# Regbot.net
KiCad netlist of a schematic drawn in EAGLE
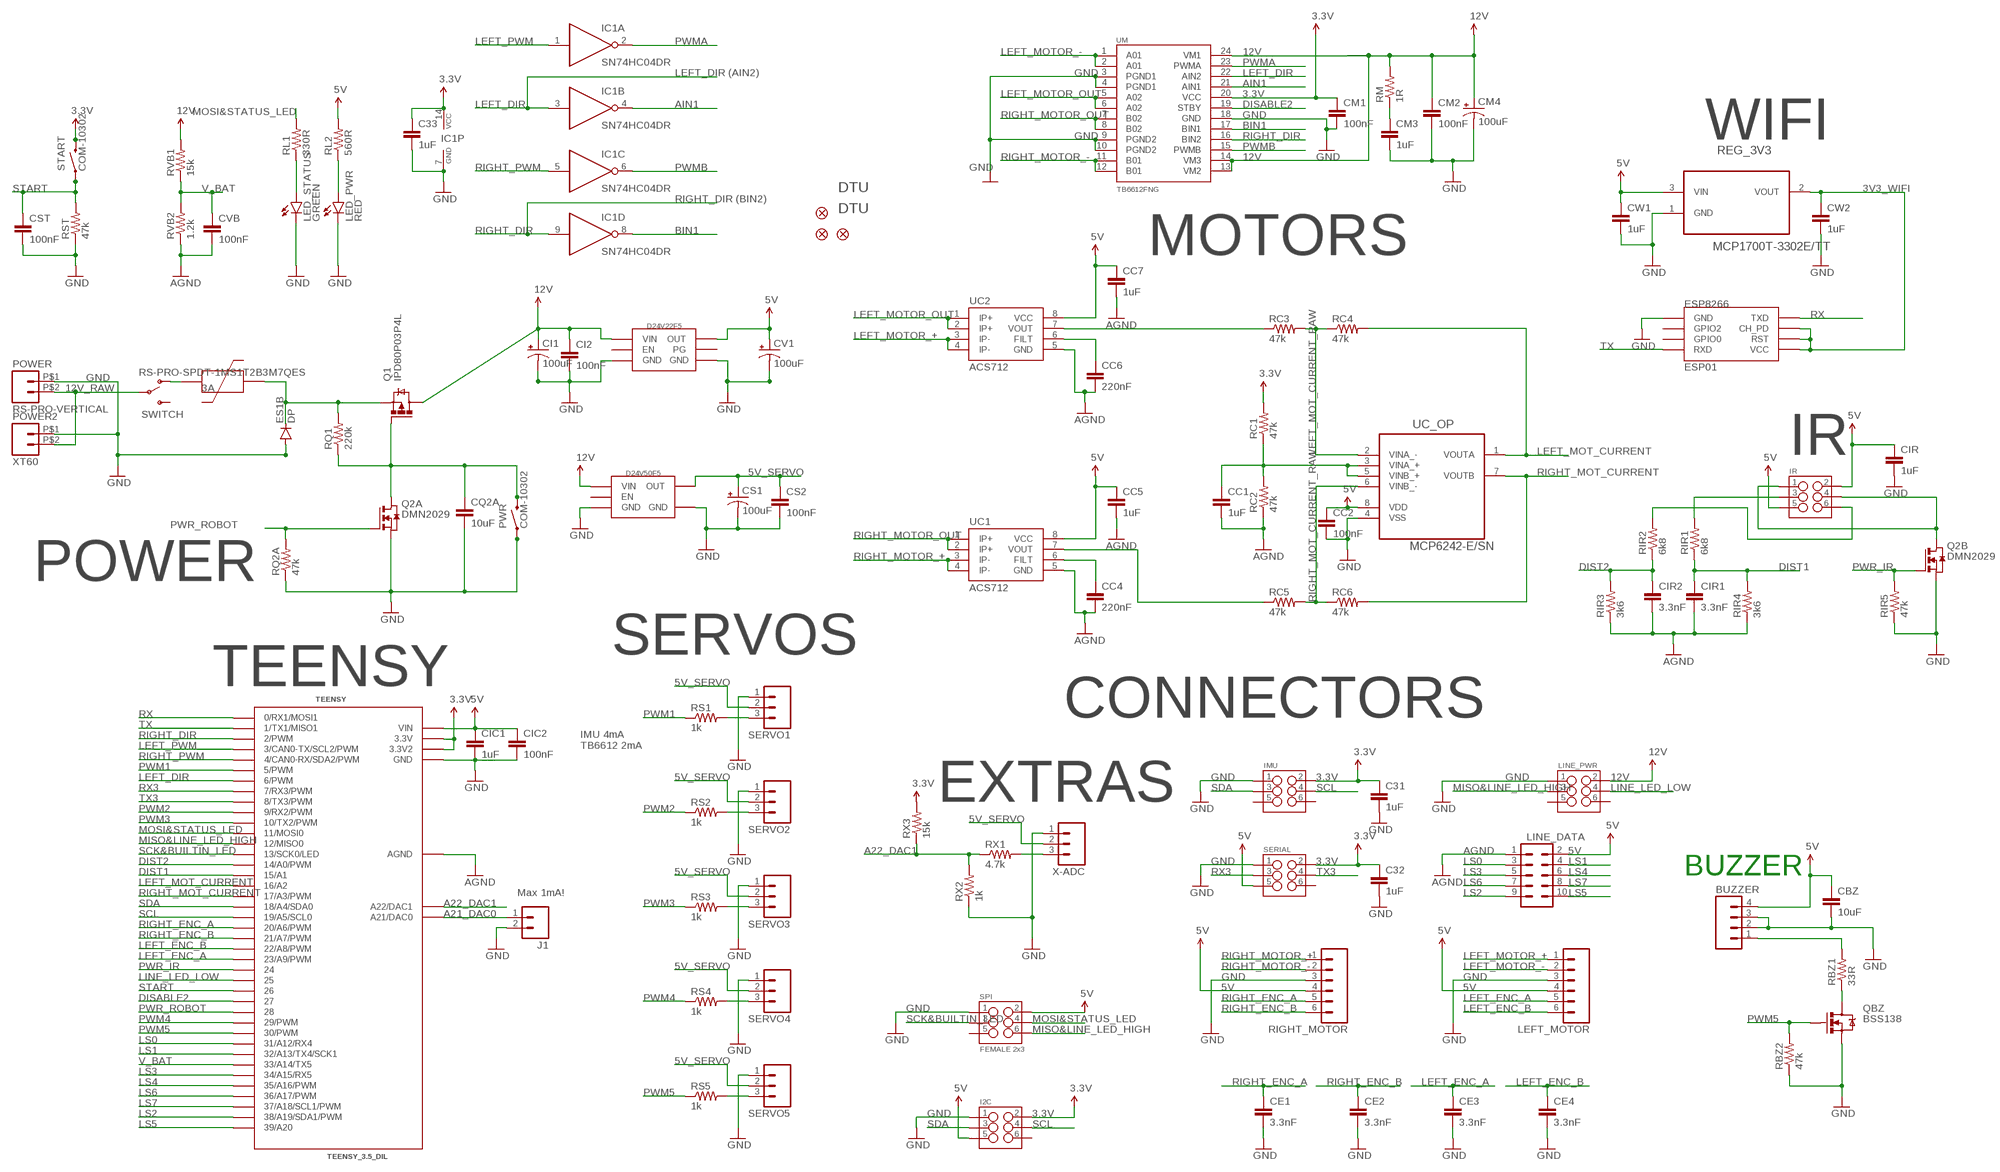
[diagram p0: schematic, sheet 1]

(export (version "E")
  (design (tool "Eeschema 10.0.6"))
  (components
    (comp (ref "BUZZER")
      (value "M04POLAR")
      (footprint "eagle-import:MOLEX-1X4")
      (libsource (lib "eagle-import") (part "M04POLAR"))
    )
    (comp (ref "C31")
      (value "1uF")
      (footprint "eagle-import:0805")
      (libsource (lib "eagle-import") (part "SparkFun-Passives_CAP0805"))
    )
    (comp (ref "C32")
      (value "1uF")
      (footprint "eagle-import:0805")
      (libsource (lib "eagle-import") (part "CAP0805"))
    )
    (comp (ref "C33")
      (value "1uF")
      (footprint "eagle-import:0805")
      (libsource (lib "eagle-import") (part "CAP0805"))
    )
    (comp (ref "CBZ")
      (value "10uF")
      (footprint "eagle-import:1210")
      (libsource (lib "eagle-import") (part "CAP1210"))
    )
    (comp (ref "CC1")
      (value "1uF")
      (footprint "eagle-import:0805")
      (libsource (lib "eagle-import") (part "SparkFun-Passives_CAP0805"))
    )
    (comp (ref "CC2")
      (value "100nF")
      (footprint "eagle-import:0805")
      (libsource (lib "eagle-import") (part "SparkFun-Passives_CAP0805"))
    )
    (comp (ref "CC4")
      (value "220nF")
      (footprint "eagle-import:0805")
      (libsource (lib "eagle-import") (part "SparkFun-Passives_CAP0805"))
    )
    (comp (ref "CC5")
      (value "1uF")
      (footprint "eagle-import:0805")
      (libsource (lib "eagle-import") (part "SparkFun-Passives_CAP0805"))
    )
    (comp (ref "CC6")
      (value "220nF")
      (footprint "eagle-import:0805")
      (libsource (lib "eagle-import") (part "SparkFun-Passives_CAP0805"))
    )
    (comp (ref "CC7")
      (value "1uF")
      (footprint "eagle-import:0805")
      (libsource (lib "eagle-import") (part "SparkFun-Passives_CAP0805"))
    )
    (comp (ref "CE1")
      (value "3.3nF")
      (footprint "eagle-import:0805")
      (libsource (lib "eagle-import") (part "SparkFun-Passives_CAP0805"))
    )
    (comp (ref "CE2")
      (value "3.3nF")
      (footprint "eagle-import:0805")
      (libsource (lib "eagle-import") (part "SparkFun-Passives_CAP0805"))
    )
    (comp (ref "CE3")
      (value "3.3nF")
      (footprint "eagle-import:0805")
      (libsource (lib "eagle-import") (part "SparkFun-Passives_CAP0805"))
    )
    (comp (ref "CE4")
      (value "3.3nF")
      (footprint "eagle-import:0805")
      (libsource (lib "eagle-import") (part "SparkFun-Passives_CAP0805"))
    )
    (comp (ref "CI1")
      (value "100uF")
      (footprint "eagle-import:PANASONIC_D_XL")
      (libsource (lib "eagle-import") (part "PANASONIC_D"))
    )
    (comp (ref "CI2")
      (value "100nF")
      (footprint "eagle-import:0805")
      (libsource (lib "eagle-import") (part "SparkFun-Passives_CAP0805"))
    )
    (comp (ref "CIC1")
      (value "1uF")
      (footprint "eagle-import:0805")
      (libsource (lib "eagle-import") (part "CAP0805"))
    )
    (comp (ref "CIC2")
      (value "100nF")
      (footprint "eagle-import:0805")
      (libsource (lib "eagle-import") (part "SparkFun-Passives_CAP0805"))
    )
    (comp (ref "CIR")
      (value "1uF")
      (footprint "eagle-import:0805")
      (libsource (lib "eagle-import") (part "SparkFun-Passives_CAP0805"))
    )
    (comp (ref "CIR1")
      (value "3.3nF")
      (footprint "eagle-import:0805")
      (libsource (lib "eagle-import") (part "SparkFun-Passives_CAP0805"))
    )
    (comp (ref "CIR2")
      (value "3.3nF")
      (footprint "eagle-import:0805")
      (libsource (lib "eagle-import") (part "SparkFun-Passives_CAP0805"))
    )
    (comp (ref "CM1")
      (value "100nF")
      (footprint "eagle-import:0805")
      (libsource (lib "eagle-import") (part "SparkFun-Passives_CAP0805"))
    )
    (comp (ref "CM2")
      (value "100nF")
      (footprint "eagle-import:0805")
      (libsource (lib "eagle-import") (part "SparkFun-Passives_CAP0805"))
    )
    (comp (ref "CM3")
      (value "1uF")
      (footprint "eagle-import:0805")
      (libsource (lib "eagle-import") (part "SparkFun-Passives_CAP0805"))
    )
    (comp (ref "CM4")
      (value "100uF")
      (footprint "eagle-import:PANASONIC_D_XL")
      (libsource (lib "eagle-import") (part "PANASONIC_D"))
    )
    (comp (ref "CQ2A")
      (value "10uF")
      (footprint "eagle-import:1210")
      (libsource (lib "eagle-import") (part "CAP1210"))
    )
    (comp (ref "CS1")
      (value "100uF")
      (footprint "eagle-import:PANASONIC_D_XL")
      (libsource (lib "eagle-import") (part "PANASONIC_D"))
    )
    (comp (ref "CS2")
      (value "100nF")
      (footprint "eagle-import:0805")
      (libsource (lib "eagle-import") (part "SparkFun-Passives_CAP0805"))
    )
    (comp (ref "CST")
      (value "100nF")
      (footprint "eagle-import:0805")
      (libsource (lib "eagle-import") (part "SparkFun-Passives_CAP0805"))
    )
    (comp (ref "CV1")
      (value "100uF")
      (footprint "eagle-import:PANASONIC_D_XL")
      (libsource (lib "eagle-import") (part "PANASONIC_D"))
    )
    (comp (ref "CVB")
      (value "100nF")
      (footprint "eagle-import:0805")
      (libsource (lib "eagle-import") (part "SparkFun-Passives_CAP0805"))
    )
    (comp (ref "CW1")
      (value "1uF")
      (footprint "eagle-import:0805")
      (libsource (lib "eagle-import") (part "SparkFun-Passives_CAP0805"))
    )
    (comp (ref "CW2")
      (value "1uF")
      (footprint "eagle-import:0805")
      (libsource (lib "eagle-import") (part "SparkFun-Passives_CAP0805"))
    )
    (comp (ref "D24V22F5")
      (value "POLOLU_D24V22")
      (footprint "eagle-import:D24V22")
      (libsource (lib "eagle-import") (part "POLOLU_D24V22"))
    )
    (comp (ref "D24V50F5")
      (value "POLOLU_D24V50")
      (footprint "eagle-import:D24V50")
      (libsource (lib "eagle-import") (part "POLOLU_D24V50"))
    )
    (comp (ref "DP")
      (value "ES1B")
      (footprint "eagle-import:SMA-DIODE")
      (libsource (lib "eagle-import") (part "DIODESMA"))
    )
    (comp (ref "ESP8266")
      (value "ESP01")
      (footprint "eagle-import:ESP01")
      (libsource (lib "eagle-import") (part "ESP01"))
    )
    (comp (ref "FD1")
      (value "FIDUCIAL1X2")
      (footprint "eagle-import:FIDUCIAL-1X2")
      (libsource (lib "eagle-import") (part "FIDUCIAL1X2"))
    )
    (comp (ref "FD2")
      (value "FIDUCIAL1X2")
      (footprint "eagle-import:FIDUCIAL-1X2")
      (libsource (lib "eagle-import") (part "FIDUCIAL1X2"))
    )
    (comp (ref "FD3")
      (value "FIDUCIAL1X2")
      (footprint "eagle-import:FIDUCIAL-1X2")
      (libsource (lib "eagle-import") (part "FIDUCIAL1X2"))
    )
    (comp (ref "I2C")
      (value "M03X2SHROUD")
      (footprint "eagle-import:2X3-SHROUDED")
      (libsource (lib "eagle-import") (part "M03X2SHROUD"))
    )
    (comp (ref "IC1")
      (value "SN74HC04DR")
      (footprint "eagle-import:SO14")
      (libsource (lib "eagle-import") (part "7404DHC"))
    )
    (comp (ref "IMU")
      (value "M03X2SHROUD")
      (footprint "eagle-import:2X3-SHROUDED")
      (libsource (lib "eagle-import") (part "M03X2SHROUD"))
    )
    (comp (ref "IR")
      (value "M03X2SHROUD")
      (footprint "eagle-import:2X3-SHROUDED")
      (libsource (lib "eagle-import") (part "M03X2SHROUD"))
    )
    (comp (ref "J1")
      (value "M02PTH")
      (footprint "eagle-import:1X02")
      (libsource (lib "eagle-import") (part "M02PTH"))
    )
    (comp (ref "LED_PWR")
      (value "RED")
      (footprint "eagle-import:LED-1206")
      (libsource (lib "eagle-import") (part "LED1206"))
    )
    (comp (ref "LED_STATUS")
      (value "GREEN")
      (footprint "eagle-import:LED-1206")
      (libsource (lib "eagle-import") (part "LED1206"))
    )
    (comp (ref "LEFT_MOTOR")
      (value "M06SILK_FEMALE_PTH")
      (footprint "eagle-import:1X06")
      (libsource (lib "eagle-import") (part "M06SILK_FEMALE_PTH"))
    )
    (comp (ref "LINE_DATA")
      (value "M05X2SHD")
      (footprint "eagle-import:2X5-SHROUDED")
      (libsource (lib "eagle-import") (part "M05X2SHD"))
    )
    (comp (ref "LINE_PWR")
      (value "M03X2SHROUD")
      (footprint "eagle-import:2X3-SHROUDED")
      (libsource (lib "eagle-import") (part "M03X2SHROUD"))
    )
    (comp (ref "MAIN_FUSE")
      (value "SMF_OMNI-BLOK_FUSE_BLOCK")
      (footprint "eagle-import:SMF_OMNI-BLOK_FUSE_BLOCK")
      (libsource (lib "eagle-import") (part "SMF_OMNI-BLOK_FUSE_BLOCK"))
    )
    (comp (ref "POWER")
      (value "RS-PRO-VERTICAL")
      (footprint "eagle-import:RS-PRO-VERTICAL")
      (fields (field (name "PURPOSE") "DYSE"))
      (libsource (lib "eagle-import") (part "RS-PRO-VERTICAL"))
    )
    (comp (ref "POWER2")
      (value "XT60")
      (footprint "eagle-import:XT60")
      (libsource (lib "eagle-import") (part "XT60"))
    )
    (comp (ref "PWR")
      (value "COM-10302")
      (footprint "eagle-import:TACTILE-PTH-12MM")
      (libsource (lib "eagle-import") (part "SWITCH-MOMENTARY"))
    )
    (comp (ref "Q1")
      (value "IPD80P03P4L")
      (footprint "eagle-import:D-PAK_TO252AA")
      (libsource (lib "eagle-import") (part "IRF?5305R"))
    )
    (comp (ref "Q2")
      (value "DMN2029")
      (footprint "eagle-import:SO8")
      (libsource (lib "eagle-import") (part "NMOS2SO8"))
    )
    (comp (ref "QBZ")
      (value "BSS138")
      (footprint "eagle-import:SOT23")
      (fields (field (name "PROD_ID") "TRANS-00830"))
      (libsource (lib "eagle-import") (part "MOSFET-NCHANNELBSS138"))
    )
    (comp (ref "RBZ1")
      (value "33R")
      (footprint "eagle-import:0805")
      (libsource (lib "eagle-import") (part "RESISTOR0805-RES"))
    )
    (comp (ref "RBZ2")
      (value "47k")
      (footprint "eagle-import:0805")
      (libsource (lib "eagle-import") (part "RESISTOR0805-RES"))
    )
    (comp (ref "RC1")
      (value "47k")
      (footprint "eagle-import:0805")
      (libsource (lib "eagle-import") (part "RESISTOR0805-RES"))
    )
    (comp (ref "RC2")
      (value "47k")
      (footprint "eagle-import:0805")
      (libsource (lib "eagle-import") (part "RESISTOR0805-RES"))
    )
    (comp (ref "RC3")
      (value "47k")
      (footprint "eagle-import:0805")
      (libsource (lib "eagle-import") (part "RESISTOR0805-RES"))
    )
    (comp (ref "RC4")
      (value "47k")
      (footprint "eagle-import:0805")
      (libsource (lib "eagle-import") (part "RESISTOR0805-RES"))
    )
    (comp (ref "RC5")
      (value "47k")
      (footprint "eagle-import:0805")
      (libsource (lib "eagle-import") (part "RESISTOR0805-RES"))
    )
    (comp (ref "RC6")
      (value "47k")
      (footprint "eagle-import:0805")
      (libsource (lib "eagle-import") (part "RESISTOR0805-RES"))
    )
    (comp (ref "REG_3V3")
      (value "MCP1700T-3302E/TT")
      (footprint "eagle-import:SOT95P237X112-3N")
      (libsource (lib "eagle-import") (part "MCP1700T-3302E/TT"))
    )
    (comp (ref "RIGHT_MOTOR")
      (value "M06SILK_FEMALE_PTH")
      (footprint "eagle-import:1X06")
      (libsource (lib "eagle-import") (part "M06SILK_FEMALE_PTH"))
    )
    (comp (ref "RIR1")
      (value "6k8")
      (footprint "eagle-import:0805")
      (libsource (lib "eagle-import") (part "RESISTOR0805-RES"))
    )
    (comp (ref "RIR2")
      (value "6k8")
      (footprint "eagle-import:0805")
      (libsource (lib "eagle-import") (part "RESISTOR0805-RES"))
    )
    (comp (ref "RIR3")
      (value "3k6")
      (footprint "eagle-import:0805")
      (libsource (lib "eagle-import") (part "RESISTOR0805-RES"))
    )
    (comp (ref "RIR4")
      (value "3k6")
      (footprint "eagle-import:0805")
      (libsource (lib "eagle-import") (part "RESISTOR0805-RES"))
    )
    (comp (ref "RIR5")
      (value "47k")
      (footprint "eagle-import:0805")
      (libsource (lib "eagle-import") (part "RESISTOR0805-RES"))
    )
    (comp (ref "RL1")
      (value "330R")
      (footprint "eagle-import:0805")
      (libsource (lib "eagle-import") (part "RESISTOR0805-RES"))
    )
    (comp (ref "RL2")
      (value "560R")
      (footprint "eagle-import:0805")
      (libsource (lib "eagle-import") (part "RESISTOR0805-RES"))
    )
    (comp (ref "RM")
      (value "1R")
      (footprint "eagle-import:0805")
      (libsource (lib "eagle-import") (part "RESISTOR0805-RES"))
    )
    (comp (ref "RQ1")
      (value "220k")
      (footprint "eagle-import:0805")
      (libsource (lib "eagle-import") (part "RESISTOR0805-RES"))
    )
    (comp (ref "RQ2A")
      (value "47k")
      (footprint "eagle-import:0805")
      (libsource (lib "eagle-import") (part "RESISTOR0805-RES"))
    )
    (comp (ref "RS1")
      (value "1k")
      (footprint "eagle-import:0805")
      (libsource (lib "eagle-import") (part "RESISTOR0805-RES"))
    )
    (comp (ref "RS2")
      (value "1k")
      (footprint "eagle-import:0805")
      (libsource (lib "eagle-import") (part "RESISTOR0805-RES"))
    )
    (comp (ref "RS3")
      (value "1k")
      (footprint "eagle-import:0805")
      (libsource (lib "eagle-import") (part "RESISTOR0805-RES"))
    )
    (comp (ref "RS4")
      (value "1k")
      (footprint "eagle-import:0805")
      (libsource (lib "eagle-import") (part "RESISTOR0805-RES"))
    )
    (comp (ref "RS5")
      (value "1k")
      (footprint "eagle-import:0805")
      (libsource (lib "eagle-import") (part "RESISTOR0805-RES"))
    )
    (comp (ref "RST")
      (value "47k")
      (footprint "eagle-import:0805")
      (libsource (lib "eagle-import") (part "RESISTOR0805-RES"))
    )
    (comp (ref "RVB1")
      (value "15k")
      (footprint "eagle-import:0805")
      (libsource (lib "eagle-import") (part "RESISTOR0805-RES"))
    )
    (comp (ref "RVB2")
      (value "1.2k")
      (footprint "eagle-import:0805")
      (libsource (lib "eagle-import") (part "RESISTOR0805-RES"))
    )
    (comp (ref "RX1")
      (value "4.7k")
      (footprint "eagle-import:0805")
      (libsource (lib "eagle-import") (part "RESISTOR0805-RES"))
    )
    (comp (ref "RX2")
      (value "1k")
      (footprint "eagle-import:0805")
      (libsource (lib "eagle-import") (part "RESISTOR0805-RES"))
    )
    (comp (ref "RX3")
      (value "15k")
      (footprint "eagle-import:0805")
      (libsource (lib "eagle-import") (part "RESISTOR0805-RES"))
    )
    (comp (ref "SERIAL")
      (value "M03X2SHROUD")
      (footprint "eagle-import:2X3-SHROUDED")
      (libsource (lib "eagle-import") (part "M03X2SHROUD"))
    )
    (comp (ref "SERVO1")
      (value "M03POLAR")
      (footprint "eagle-import:MOLEX-1X3")
      (libsource (lib "eagle-import") (part "M03POLAR"))
    )
    (comp (ref "SERVO2")
      (value "M03POLAR")
      (footprint "eagle-import:MOLEX-1X3")
      (libsource (lib "eagle-import") (part "M03POLAR"))
    )
    (comp (ref "SERVO3")
      (value "M03POLAR")
      (footprint "eagle-import:MOLEX-1X3")
      (libsource (lib "eagle-import") (part "M03POLAR"))
    )
    (comp (ref "SERVO4")
      (value "M03POLAR")
      (footprint "eagle-import:MOLEX-1X3")
      (libsource (lib "eagle-import") (part "M03POLAR"))
    )
    (comp (ref "SERVO5")
      (value "M03POLAR")
      (footprint "eagle-import:MOLEX-1X3")
      (libsource (lib "eagle-import") (part "M03POLAR"))
    )
    (comp (ref "SPI")
      (value "FEMALE 2x3")
      (footprint "eagle-import:2X3")
      (libsource (lib "eagle-import") (part "M03X2FEMALE"))
    )
    (comp (ref "START")
      (value "COM-10302")
      (footprint "eagle-import:TACTILE-PTH-12MM")
      (libsource (lib "eagle-import") (part "SWITCH-MOMENTARY"))
    )
    (comp (ref "SWITCH")
      (value "RS-PRO-SPDT-1MS1T2B3M7QES")
      (footprint "eagle-import:RS-PRO-1MS1T2B3M7QES")
      (libsource (lib "eagle-import") (part "RS-PRO-SPDT-1MS1T2B3M7QES"))
    )
    (comp (ref "TEENSY")
      (value "TEENSY_3.5_DIL")
      (footprint "eagle-import:TEENSY_3.5_DIL")
      (libsource (lib "eagle-import") (part "TEENSY_3.5_DIL"))
    )
    (comp (ref "U$1")
      (value "DTUMEDIUM-9MM")
      (footprint "eagle-import:DTU-MEDIUM-9MM")
      (libsource (lib "eagle-import") (part "DTUMEDIUM-9MM"))
    )
    (comp (ref "U$2")
      (value "DTULARGE")
      (footprint "eagle-import:DTU-LARGE")
      (libsource (lib "eagle-import") (part "DTULARGE"))
    )
    (comp (ref "UC1")
      (value "ACS712")
      (footprint "eagle-import:SO08")
      (libsource (lib "eagle-import") (part "ACS712"))
    )
    (comp (ref "UC2")
      (value "ACS712")
      (footprint "eagle-import:SO08")
      (libsource (lib "eagle-import") (part "ACS712"))
    )
    (comp (ref "UC_OP")
      (value "MCP6242-E/SN")
      (footprint "eagle-import:SOIC127P600X175-8N")
      (libsource (lib "eagle-import") (part "MCP6242-E/SN"))
    )
    (comp (ref "UM")
      (value "TB6612FNG")
      (footprint "eagle-import:SSOP24")
      (libsource (lib "eagle-import") (part "TB6612FNG"))
    )
    (comp (ref "X-ADC")
      (value "M03POLAR")
      (footprint "eagle-import:MOLEX-1X3")
      (libsource (lib "eagle-import") (part "M03POLAR"))
    )
  )
  (nets
    (net (code "1") (name "/3V3_WIFI") (class "Default")
      (node (ref "CW2") (pin "1") (pinfunction "1_1") (pintype "passive"))
      (node (ref "ESP8266") (pin "CH_PD") (pinfunction "CH_PD_CH_PD") (pintype "bidirectional"))
      (node (ref "ESP8266") (pin "RST") (pinfunction "RST_RST") (pintype "bidirectional"))
      (node (ref "ESP8266") (pin "VCC") (pinfunction "VCC_VCC") (pintype "bidirectional"))
      (node (ref "REG_3V3") (pin "2") (pinfunction "VOUT_2") (pintype "output"))
    )
    (net (code "2") (name "/5V_SERVO") (class "Default")
      (node (ref "CS1") (pin "+") (pinfunction "+_+") (pintype "passive"))
      (node (ref "CS2") (pin "1") (pinfunction "1_1") (pintype "passive"))
      (node (ref "D24V50F5") (pin "P$OUT") (pinfunction "OUT_P$OUT") (pintype "bidirectional"))
      (node (ref "SERVO1") (pin "2") (pinfunction "2_2") (pintype "passive"))
      (node (ref "SERVO2") (pin "2") (pinfunction "2_2") (pintype "passive"))
      (node (ref "SERVO3") (pin "2") (pinfunction "2_2") (pintype "passive"))
      (node (ref "SERVO4") (pin "2") (pinfunction "2_2") (pintype "passive"))
      (node (ref "SERVO5") (pin "2") (pinfunction "2_2") (pintype "passive"))
      (node (ref "X-ADC") (pin "2") (pinfunction "2_2") (pintype "passive"))
    )
    (net (code "3") (name "/12V_RAW") (class "Default")
      (node (ref "POWER") (pin "P$2") (pinfunction "2_P$2") (pintype "passive"))
      (node (ref "POWER2") (pin "P$2") (pinfunction "2_P$2") (pintype "passive"))
      (node (ref "SWITCH") (pin "P$2") (pinfunction "P2_P$2") (pintype "passive"))
    )
    (net (code "4") (name "/A21_DAC0") (class "Default")
      (node (ref "J1") (pin "1") (pinfunction "1_1") (pintype "passive"))
      (node (ref "TEENSY") (pin "A21") (pinfunction "A21/DAC0_A21") (pintype "bidirectional"))
    )
    (net (code "5") (name "/A22_DAC1") (class "Default")
      (node (ref "RX1") (pin "1") (pinfunction "1_1") (pintype "passive"))
      (node (ref "RX2") (pin "2") (pinfunction "2_2") (pintype "passive"))
      (node (ref "RX3") (pin "1") (pinfunction "1_1") (pintype "passive"))
      (node (ref "TEENSY") (pin "A22") (pinfunction "A22/DAC1_A22") (pintype "bidirectional"))
    )
    (net (code "6") (name "/AIN1") (class "Default")
      (node (ref "IC1") (pin "4") (pinfunction "O_4") (pintype "output"))
      (node (ref "UM") (pin "21") (pinfunction "AIN1_21") (pintype "bidirectional"))
    )
    (net (code "7") (name "/BIN1") (class "Default")
      (node (ref "IC1") (pin "8") (pinfunction "O_8") (pintype "output"))
      (node (ref "UM") (pin "17") (pinfunction "BIN1_17") (pintype "bidirectional"))
    )
    (net (code "8") (name "/DISABLE2") (class "Default")
      (node (ref "TEENSY") (pin "27") (pinfunction "27_27") (pintype "bidirectional"))
      (node (ref "UM") (pin "19") (pinfunction "STBY_19") (pintype "bidirectional"))
    )
    (net (code "9") (name "/DIST1") (class "Default")
      (node (ref "CIR1") (pin "1") (pinfunction "1_1") (pintype "passive"))
      (node (ref "RIR1") (pin "1") (pinfunction "1_1") (pintype "passive"))
      (node (ref "RIR4") (pin "2") (pinfunction "2_2") (pintype "passive"))
      (node (ref "TEENSY") (pin "15/A1") (pinfunction "15/A1_15/A1") (pintype "bidirectional"))
    )
    (net (code "10") (name "/DIST2") (class "Default")
      (node (ref "CIR2") (pin "1") (pinfunction "1_1") (pintype "passive"))
      (node (ref "RIR2") (pin "1") (pinfunction "1_1") (pintype "passive"))
      (node (ref "RIR3") (pin "2") (pinfunction "2_2") (pintype "passive"))
      (node (ref "TEENSY") (pin "14/A0") (pinfunction "14/A0/PWM_14/A0") (pintype "bidirectional"))
    )
    (net (code "11") (name "/LEFT_DIR") (class "Default")
      (node (ref "IC1") (pin "3") (pinfunction "I_3") (pintype "input"))
      (node (ref "TEENSY") (pin "6") (pinfunction "6/PWM_6") (pintype "bidirectional"))
      (node (ref "UM") (pin "22") (pinfunction "AIN2_22") (pintype "bidirectional"))
    )
    (net (code "12") (name "/LEFT_ENC_A") (class "Default")
      (node (ref "CE3") (pin "1") (pinfunction "1_1") (pintype "passive"))
      (node (ref "LEFT_MOTOR") (pin "5") (pinfunction "5_5") (pintype "passive"))
      (node (ref "TEENSY") (pin "23/A9") (pinfunction "23/A9/PWM_23/A9") (pintype "bidirectional"))
    )
    (net (code "13") (name "/LEFT_ENC_B") (class "Default")
      (node (ref "CE4") (pin "1") (pinfunction "1_1") (pintype "passive"))
      (node (ref "LEFT_MOTOR") (pin "6") (pinfunction "6_6") (pintype "passive"))
      (node (ref "TEENSY") (pin "22/A8") (pinfunction "22/A8/PWM_22/A8") (pintype "bidirectional"))
    )
    (net (code "14") (name "/LEFT_MOTOR_+") (class "Default")
      (node (ref "LEFT_MOTOR") (pin "1") (pinfunction "1_1") (pintype "passive"))
      (node (ref "UC2") (pin "3") (pinfunction "IP-_3") (pintype "bidirectional"))
      (node (ref "UC2") (pin "4") (pinfunction "IP-_4") (pintype "bidirectional"))
    )
    (net (code "15") (name "/LEFT_MOTOR_-") (class "Default")
      (node (ref "LEFT_MOTOR") (pin "2") (pinfunction "2_2") (pintype "passive"))
      (node (ref "UM") (pin "1") (pinfunction "A01_1") (pintype "bidirectional"))
      (node (ref "UM") (pin "2") (pinfunction "A01_2") (pintype "bidirectional"))
    )
    (net (code "16") (name "/LEFT_MOTOR_OUT") (class "Default")
      (node (ref "UC2") (pin "1") (pinfunction "IP+_1") (pintype "bidirectional"))
      (node (ref "UC2") (pin "2") (pinfunction "IP+_2") (pintype "bidirectional"))
      (node (ref "UM") (pin "5") (pinfunction "A02_5") (pintype "bidirectional"))
      (node (ref "UM") (pin "6") (pinfunction "A02_6") (pintype "bidirectional"))
    )
    (net (code "17") (name "/LEFT_MOT_CURRENT") (class "Default")
      (node (ref "RC4") (pin "2") (pinfunction "2_2") (pintype "passive"))
      (node (ref "TEENSY") (pin "16/A2") (pinfunction "16/A2_16/A2") (pintype "bidirectional"))
      (node (ref "UC_OP") (pin "1") (pinfunction "VOUTA_1") (pintype "output"))
    )
    (net (code "18") (name "/LEFT_MOT_CURRENT_RAW") (class "Default")
      (node (ref "RC3") (pin "2") (pinfunction "2_2") (pintype "passive"))
      (node (ref "RC4") (pin "1") (pinfunction "1_1") (pintype "passive"))
      (node (ref "UC_OP") (pin "2") (pinfunction "VINA_-_2") (pintype "input"))
    )
    (net (code "19") (name "/LEFT_PWM") (class "Default")
      (node (ref "IC1") (pin "1") (pinfunction "I_1") (pintype "input"))
      (node (ref "TEENSY") (pin "3") (pinfunction "3/CAN0-TX/SCL2/PWM_3") (pintype "bidirectional"))
    )
    (net (code "20") (name "/LINE_LED_LOW") (class "Default")
      (node (ref "LINE_PWR") (pin "4") (pinfunction "4_4") (pintype "bidirectional"))
      (node (ref "TEENSY") (pin "25") (pinfunction "25_25") (pintype "bidirectional"))
    )
    (net (code "21") (name "/LS0") (class "Default")
      (node (ref "LINE_DATA") (pin "3") (pinfunction "3_3") (pintype "passive"))
      (node (ref "TEENSY") (pin "31/A12") (pinfunction "31/A12/RX4_31/A12") (pintype "bidirectional"))
    )
    (net (code "22") (name "/LS1") (class "Default")
      (node (ref "LINE_DATA") (pin "4") (pinfunction "4_4") (pintype "passive"))
      (node (ref "TEENSY") (pin "32/A13") (pinfunction "32/A13/TX4/SCK1_32/A13") (pintype "bidirectional"))
    )
    (net (code "23") (name "/LS2") (class "Default")
      (node (ref "LINE_DATA") (pin "9") (pinfunction "9_9") (pintype "passive"))
      (node (ref "TEENSY") (pin "38/A19") (pinfunction "38/A19/SDA1/PWM_38/A19") (pintype "bidirectional"))
    )
    (net (code "24") (name "/LS3") (class "Default")
      (node (ref "LINE_DATA") (pin "5") (pinfunction "5_5") (pintype "passive"))
      (node (ref "TEENSY") (pin "34/A15") (pinfunction "34/A15/RX5_34/A15") (pintype "bidirectional"))
    )
    (net (code "25") (name "/LS4") (class "Default")
      (node (ref "LINE_DATA") (pin "6") (pinfunction "6_6") (pintype "passive"))
      (node (ref "TEENSY") (pin "35/A16") (pinfunction "35/A16/PWM_35/A16") (pintype "bidirectional"))
    )
    (net (code "26") (name "/LS5") (class "Default")
      (node (ref "LINE_DATA") (pin "10") (pinfunction "10_10") (pintype "passive"))
      (node (ref "TEENSY") (pin "39/A20") (pinfunction "39/A20_39/A20") (pintype "bidirectional"))
    )
    (net (code "27") (name "/LS6") (class "Default")
      (node (ref "LINE_DATA") (pin "7") (pinfunction "7_7") (pintype "passive"))
      (node (ref "TEENSY") (pin "36/A17") (pinfunction "36/A17/PWM_36/A17") (pintype "bidirectional"))
    )
    (net (code "28") (name "/LS7") (class "Default")
      (node (ref "LINE_DATA") (pin "8") (pinfunction "8_8") (pintype "passive"))
      (node (ref "TEENSY") (pin "37/A18") (pinfunction "37/A18/SCL1/PWM_37/A18") (pintype "bidirectional"))
    )
    (net (code "29") (name "/MISO&LINE_LED_HIGH") (class "Default")
      (node (ref "LINE_PWR") (pin "3") (pinfunction "3_3") (pintype "bidirectional"))
      (node (ref "SPI") (pin "6") (pinfunction "6_6") (pintype "bidirectional"))
      (node (ref "TEENSY") (pin "12") (pinfunction "12/MISO0_12") (pintype "bidirectional"))
    )
    (net (code "30") (name "/MOSI&STATUS_LED") (class "Default")
      (node (ref "RL1") (pin "2") (pinfunction "2_2") (pintype "passive"))
      (node (ref "SPI") (pin "4") (pinfunction "4_4") (pintype "bidirectional"))
      (node (ref "TEENSY") (pin "11") (pinfunction "11/MOSI0_11") (pintype "bidirectional"))
    )
    (net (code "31") (name "/PWM1") (class "Default")
      (node (ref "RS1") (pin "1") (pinfunction "1_1") (pintype "passive"))
      (node (ref "TEENSY") (pin "5") (pinfunction "5/PWM_5") (pintype "bidirectional"))
    )
    (net (code "32") (name "/PWM2") (class "Default")
      (node (ref "RS2") (pin "1") (pinfunction "1_1") (pintype "passive"))
      (node (ref "TEENSY") (pin "9") (pinfunction "9/RX2/PWM_9") (pintype "bidirectional"))
    )
    (net (code "33") (name "/PWM3") (class "Default")
      (node (ref "RS3") (pin "1") (pinfunction "1_1") (pintype "passive"))
      (node (ref "TEENSY") (pin "10") (pinfunction "10/TX2/PWM_10") (pintype "bidirectional"))
    )
    (net (code "34") (name "/PWM4") (class "Default")
      (node (ref "RS4") (pin "1") (pinfunction "1_1") (pintype "passive"))
      (node (ref "TEENSY") (pin "29") (pinfunction "29/PWM_29") (pintype "bidirectional"))
    )
    (net (code "35") (name "/PWM5") (class "Default")
      (node (ref "QBZ") (pin "1") (pinfunction "G_1") (pintype "passive"))
      (node (ref "RBZ2") (pin "2") (pinfunction "2_2") (pintype "passive"))
      (node (ref "RS5") (pin "1") (pinfunction "1_1") (pintype "passive"))
      (node (ref "TEENSY") (pin "30") (pinfunction "30/PWM_30") (pintype "bidirectional"))
    )
    (net (code "36") (name "/PWMA") (class "Default")
      (node (ref "IC1") (pin "2") (pinfunction "O_2") (pintype "output"))
      (node (ref "UM") (pin "23") (pinfunction "PWMA_23") (pintype "bidirectional"))
    )
    (net (code "37") (name "/PWMB") (class "Default")
      (node (ref "IC1") (pin "6") (pinfunction "O_6") (pintype "output"))
      (node (ref "UM") (pin "15") (pinfunction "PWMB_15") (pintype "bidirectional"))
    )
    (net (code "38") (name "/PWR_IR") (class "Default")
      (node (ref "Q2") (pin "4") (pinfunction "G_4") (pintype "passive"))
      (node (ref "RIR5") (pin "2") (pinfunction "2_2") (pintype "passive"))
      (node (ref "TEENSY") (pin "24") (pinfunction "24_24") (pintype "bidirectional"))
    )
    (net (code "39") (name "/PWR_ROBOT") (class "Default")
      (node (ref "Q2") (pin "2") (pinfunction "G_2") (pintype "passive"))
      (node (ref "RQ2A") (pin "2") (pinfunction "2_2") (pintype "passive"))
      (node (ref "TEENSY") (pin "28") (pinfunction "28_28") (pintype "bidirectional"))
    )
    (net (code "40") (name "/RIGHT_DIR") (class "Default")
      (node (ref "IC1") (pin "9") (pinfunction "I_9") (pintype "input"))
      (node (ref "TEENSY") (pin "2") (pinfunction "2/PWM_2") (pintype "bidirectional"))
      (node (ref "UM") (pin "16") (pinfunction "BIN2_16") (pintype "bidirectional"))
    )
    (net (code "41") (name "/RIGHT_ENC_A") (class "Default")
      (node (ref "CE1") (pin "1") (pinfunction "1_1") (pintype "passive"))
      (node (ref "RIGHT_MOTOR") (pin "5") (pinfunction "5_5") (pintype "passive"))
      (node (ref "TEENSY") (pin "20/A6") (pinfunction "20/A6/PWM_20/A6") (pintype "bidirectional"))
    )
    (net (code "42") (name "/RIGHT_ENC_B") (class "Default")
      (node (ref "CE2") (pin "1") (pinfunction "1_1") (pintype "passive"))
      (node (ref "RIGHT_MOTOR") (pin "6") (pinfunction "6_6") (pintype "passive"))
      (node (ref "TEENSY") (pin "21/A7") (pinfunction "21/A7/PWM_21/A7") (pintype "bidirectional"))
    )
    (net (code "43") (name "/RIGHT_MOTOR_+") (class "Default")
      (node (ref "RIGHT_MOTOR") (pin "1") (pinfunction "1_1") (pintype "passive"))
      (node (ref "UC1") (pin "3") (pinfunction "IP-_3") (pintype "bidirectional"))
      (node (ref "UC1") (pin "4") (pinfunction "IP-_4") (pintype "bidirectional"))
    )
    (net (code "44") (name "/RIGHT_MOTOR_-") (class "Default")
      (node (ref "RIGHT_MOTOR") (pin "2") (pinfunction "2_2") (pintype "passive"))
      (node (ref "UM") (pin "11") (pinfunction "B01_11") (pintype "bidirectional"))
      (node (ref "UM") (pin "12") (pinfunction "B01_12") (pintype "bidirectional"))
    )
    (net (code "45") (name "/RIGHT_MOTOR_OUT") (class "Default")
      (node (ref "UC1") (pin "1") (pinfunction "IP+_1") (pintype "bidirectional"))
      (node (ref "UC1") (pin "2") (pinfunction "IP+_2") (pintype "bidirectional"))
      (node (ref "UM") (pin "7") (pinfunction "B02_7") (pintype "bidirectional"))
      (node (ref "UM") (pin "8") (pinfunction "B02_8") (pintype "bidirectional"))
    )
    (net (code "46") (name "/RIGHT_MOT_CURRENT") (class "Default")
      (node (ref "RC6") (pin "2") (pinfunction "2_2") (pintype "passive"))
      (node (ref "TEENSY") (pin "17/A3") (pinfunction "17/A3/PWM_17/A3") (pintype "bidirectional"))
      (node (ref "UC_OP") (pin "7") (pinfunction "VOUTB_7") (pintype "output"))
    )
    (net (code "47") (name "/RIGHT_MOT_CURRENT_RAW") (class "Default")
      (node (ref "RC5") (pin "2") (pinfunction "2_2") (pintype "passive"))
      (node (ref "RC6") (pin "1") (pinfunction "1_1") (pintype "passive"))
      (node (ref "UC_OP") (pin "6") (pinfunction "VINB_-_6") (pintype "input"))
    )
    (net (code "48") (name "/RIGHT_PWM") (class "Default")
      (node (ref "IC1") (pin "5") (pinfunction "I_5") (pintype "input"))
      (node (ref "TEENSY") (pin "4") (pinfunction "4/CAN0-RX/SDA2/PWM_4") (pintype "bidirectional"))
    )
    (net (code "49") (name "/RX") (class "Default")
      (node (ref "ESP8266") (pin "TX") (pinfunction "TXD_TX") (pintype "bidirectional"))
      (node (ref "TEENSY") (pin "0") (pinfunction "0/RX1/MOSI1_0") (pintype "bidirectional"))
    )
    (net (code "50") (name "/RX3") (class "Default")
      (node (ref "SERIAL") (pin "3") (pinfunction "3_3") (pintype "bidirectional"))
      (node (ref "TEENSY") (pin "7") (pinfunction "7/RX3/PWM_7") (pintype "bidirectional"))
    )
    (net (code "51") (name "/SCK&BUILTIN_LED") (class "Default")
      (node (ref "SPI") (pin "3") (pinfunction "3_3") (pintype "bidirectional"))
      (node (ref "TEENSY") (pin "13") (pinfunction "13/SCK0/LED_13") (pintype "bidirectional"))
    )
    (net (code "52") (name "/SCL") (class "Default")
      (node (ref "I2C") (pin "4") (pinfunction "4_4") (pintype "bidirectional"))
      (node (ref "IMU") (pin "4") (pinfunction "4_4") (pintype "bidirectional"))
      (node (ref "TEENSY") (pin "19/A5") (pinfunction "19/A5/SCL0_19/A5") (pintype "bidirectional"))
    )
    (net (code "53") (name "/SDA") (class "Default")
      (node (ref "I2C") (pin "3") (pinfunction "3_3") (pintype "bidirectional"))
      (node (ref "IMU") (pin "3") (pinfunction "3_3") (pintype "bidirectional"))
      (node (ref "TEENSY") (pin "18/A4") (pinfunction "18/A4/SDA0_18/A4") (pintype "bidirectional"))
    )
    (net (code "54") (name "/START") (class "Default")
      (node (ref "CST") (pin "1") (pinfunction "1_1") (pintype "passive"))
      (node (ref "RST") (pin "2") (pinfunction "2_2") (pintype "passive"))
      (node (ref "START") (pin "1") (pinfunction "1_1") (pintype "passive"))
      (node (ref "START") (pin "2") (pinfunction "2_2") (pintype "passive"))
      (node (ref "TEENSY") (pin "26") (pinfunction "26_26") (pintype "bidirectional"))
    )
    (net (code "55") (name "/TX") (class "Default")
      (node (ref "ESP8266") (pin "RX") (pinfunction "RXD_RX") (pintype "bidirectional"))
      (node (ref "TEENSY") (pin "1") (pinfunction "1/TX1/MISO1_1") (pintype "bidirectional"))
    )
    (net (code "56") (name "/TX3") (class "Default")
      (node (ref "SERIAL") (pin "4") (pinfunction "4_4") (pintype "bidirectional"))
      (node (ref "TEENSY") (pin "8") (pinfunction "8/TX3/PWM_8") (pintype "bidirectional"))
    )
    (net (code "57") (name "/V_BAT") (class "Default")
      (node (ref "CVB") (pin "1") (pinfunction "1_1") (pintype "passive"))
      (node (ref "RVB1") (pin "1") (pinfunction "1_1") (pintype "passive"))
      (node (ref "RVB2") (pin "2") (pinfunction "2_2") (pintype "passive"))
      (node (ref "TEENSY") (pin "33/A14") (pinfunction "33/A14/TX5_33/A14") (pintype "bidirectional"))
    )
    (net (code "58") (name "3.3V") (class "Default")
      (node (ref "C31") (pin "1") (pinfunction "1_1") (pintype "passive"))
      (node (ref "C32") (pin "1") (pinfunction "1_1") (pintype "passive"))
      (node (ref "C33") (pin "1") (pinfunction "1_1") (pintype "passive"))
      (node (ref "CM1") (pin "1") (pinfunction "1_1") (pintype "passive"))
      (node (ref "I2C") (pin "2") (pinfunction "2_2") (pintype "bidirectional"))
      (node (ref "IC1") (pin "14") (pinfunction "VCC_14") (pintype "power_in"))
      (node (ref "IMU") (pin "2") (pinfunction "2_2") (pintype "bidirectional"))
      (node (ref "RC1") (pin "2") (pinfunction "2_2") (pintype "passive"))
      (node (ref "RX3") (pin "2") (pinfunction "2_2") (pintype "passive"))
      (node (ref "SERIAL") (pin "2") (pinfunction "2_2") (pintype "bidirectional"))
      (node (ref "START") (pin "3") (pinfunction "3_3") (pintype "passive"))
      (node (ref "START") (pin "4") (pinfunction "4_4") (pintype "passive"))
      (node (ref "TEENSY") (pin "3.3V") (pinfunction "3.3V_3.3V") (pintype "power_in"))
      (node (ref "TEENSY") (pin "3.3V3") (pinfunction "3.3V2_3.3V3") (pintype "power_in"))
      (node (ref "UM") (pin "20") (pinfunction "VCC_20") (pintype "bidirectional"))
    )
    (net (code "59") (name "5V") (class "Default")
      (node (ref "BUZZER") (pin "4") (pinfunction "4_4") (pintype "passive"))
      (node (ref "CBZ") (pin "1") (pinfunction "1_1") (pintype "passive"))
      (node (ref "CC2") (pin "1") (pinfunction "1_1") (pintype "passive"))
      (node (ref "CC5") (pin "1") (pinfunction "1_1") (pintype "passive"))
      (node (ref "CC7") (pin "1") (pinfunction "1_1") (pintype "passive"))
      (node (ref "CIC1") (pin "1") (pinfunction "1_1") (pintype "passive"))
      (node (ref "CIC2") (pin "1") (pinfunction "1_1") (pintype "passive"))
      (node (ref "CIR") (pin "1") (pinfunction "1_1") (pintype "passive"))
      (node (ref "CV1") (pin "+") (pinfunction "+_+") (pintype "passive"))
      (node (ref "CW1") (pin "1") (pinfunction "1_1") (pintype "passive"))
      (node (ref "D24V22F5") (pin "P$OUT") (pinfunction "OUT_P$OUT") (pintype "bidirectional"))
      (node (ref "I2C") (pin "5") (pinfunction "5_5") (pintype "bidirectional"))
      (node (ref "IR") (pin "2") (pinfunction "2_2") (pintype "bidirectional"))
      (node (ref "IR") (pin "5") (pinfunction "5_5") (pintype "bidirectional"))
      (node (ref "LEFT_MOTOR") (pin "4") (pinfunction "4_4") (pintype "passive"))
      (node (ref "LINE_DATA") (pin "2") (pinfunction "2_2") (pintype "passive"))
      (node (ref "REG_3V3") (pin "3") (pinfunction "VIN_3") (pintype "input"))
      (node (ref "RIGHT_MOTOR") (pin "4") (pinfunction "4_4") (pintype "passive"))
      (node (ref "RL2") (pin "2") (pinfunction "2_2") (pintype "passive"))
      (node (ref "SERIAL") (pin "5") (pinfunction "5_5") (pintype "bidirectional"))
      (node (ref "SPI") (pin "2") (pinfunction "2_2") (pintype "bidirectional"))
      (node (ref "TEENSY") (pin "VIN") (pinfunction "VIN_VIN") (pintype "power_in"))
      (node (ref "UC1") (pin "8") (pinfunction "VCC_8") (pintype "bidirectional"))
      (node (ref "UC2") (pin "8") (pinfunction "VCC_8") (pintype "bidirectional"))
      (node (ref "UC_OP") (pin "8") (pinfunction "VDD_8") (pintype "power_in"))
    )
    (net (code "60") (name "12V") (class "Default")
      (node (ref "CI1") (pin "+") (pinfunction "+_+") (pintype "passive"))
      (node (ref "CI2") (pin "1") (pinfunction "1_1") (pintype "passive"))
      (node (ref "CM2") (pin "1") (pinfunction "1_1") (pintype "passive"))
      (node (ref "CM4") (pin "+") (pinfunction "+_+") (pintype "passive"))
      (node (ref "D24V22F5") (pin "P$VIN") (pinfunction "VIN_P$VIN") (pintype "bidirectional"))
      (node (ref "D24V50F5") (pin "P$VIN") (pinfunction "VIN_P$VIN") (pintype "bidirectional"))
      (node (ref "LINE_PWR") (pin "2") (pinfunction "2_2") (pintype "bidirectional"))
      (node (ref "Q1") (pin "4") (pinfunction "D_4") (pintype "passive"))
      (node (ref "RM") (pin "2") (pinfunction "2_2") (pintype "passive"))
      (node (ref "RVB1") (pin "2") (pinfunction "2_2") (pintype "passive"))
      (node (ref "UM") (pin "13") (pinfunction "VM2_13") (pintype "bidirectional"))
      (node (ref "UM") (pin "14") (pinfunction "VM3_14") (pintype "bidirectional"))
      (node (ref "UM") (pin "24") (pinfunction "VM1_24") (pintype "bidirectional"))
    )
    (net (code "61") (name "AGND") (class "Default")
      (node (ref "CC1") (pin "2") (pinfunction "2_2") (pintype "passive"))
      (node (ref "CC4") (pin "2") (pinfunction "2_2") (pintype "passive"))
      (node (ref "CC5") (pin "2") (pinfunction "2_2") (pintype "passive"))
      (node (ref "CC6") (pin "2") (pinfunction "2_2") (pintype "passive"))
      (node (ref "CC7") (pin "2") (pinfunction "2_2") (pintype "passive"))
      (node (ref "CIR1") (pin "2") (pinfunction "2_2") (pintype "passive"))
      (node (ref "CIR2") (pin "2") (pinfunction "2_2") (pintype "passive"))
      (node (ref "CVB") (pin "2") (pinfunction "2_2") (pintype "passive"))
      (node (ref "LINE_DATA") (pin "1") (pinfunction "1_1") (pintype "passive"))
      (node (ref "RC2") (pin "1") (pinfunction "1_1") (pintype "passive"))
      (node (ref "RIR3") (pin "1") (pinfunction "1_1") (pintype "passive"))
      (node (ref "RIR4") (pin "1") (pinfunction "1_1") (pintype "passive"))
      (node (ref "RVB2") (pin "1") (pinfunction "1_1") (pintype "passive"))
      (node (ref "TEENSY") (pin "AGND") (pinfunction "AGND_AGND") (pintype "power_in"))
      (node (ref "UC1") (pin "5") (pinfunction "GND_5") (pintype "bidirectional"))
      (node (ref "UC2") (pin "5") (pinfunction "GND_5") (pintype "bidirectional"))
    )
    (net (code "62") (name "GND") (class "Default")
      (node (ref "BUZZER") (pin "2") (pinfunction "2_2") (pintype "passive"))
      (node (ref "BUZZER") (pin "3") (pinfunction "3_3") (pintype "passive"))
      (node (ref "C31") (pin "2") (pinfunction "2_2") (pintype "passive"))
      (node (ref "C32") (pin "2") (pinfunction "2_2") (pintype "passive"))
      (node (ref "C33") (pin "2") (pinfunction "2_2") (pintype "passive"))
      (node (ref "CBZ") (pin "2") (pinfunction "2_2") (pintype "passive"))
      (node (ref "CC2") (pin "2") (pinfunction "2_2") (pintype "passive"))
      (node (ref "CE1") (pin "2") (pinfunction "2_2") (pintype "passive"))
      (node (ref "CE2") (pin "2") (pinfunction "2_2") (pintype "passive"))
      (node (ref "CE3") (pin "2") (pinfunction "2_2") (pintype "passive"))
      (node (ref "CE4") (pin "2") (pinfunction "2_2") (pintype "passive"))
      (node (ref "CI1") (pin "-") (pinfunction "-_-") (pintype "passive"))
      (node (ref "CI2") (pin "2") (pinfunction "2_2") (pintype "passive"))
      (node (ref "CIC1") (pin "2") (pinfunction "2_2") (pintype "passive"))
      (node (ref "CIC2") (pin "2") (pinfunction "2_2") (pintype "passive"))
      (node (ref "CIR") (pin "2") (pinfunction "2_2") (pintype "passive"))
      (node (ref "CM1") (pin "2") (pinfunction "2_2") (pintype "passive"))
      (node (ref "CM2") (pin "2") (pinfunction "2_2") (pintype "passive"))
      (node (ref "CM3") (pin "2") (pinfunction "2_2") (pintype "passive"))
      (node (ref "CM4") (pin "-") (pinfunction "-_-") (pintype "passive"))
      (node (ref "CQ2A") (pin "2") (pinfunction "2_2") (pintype "passive"))
      (node (ref "CS1") (pin "-") (pinfunction "-_-") (pintype "passive"))
      (node (ref "CS2") (pin "2") (pinfunction "2_2") (pintype "passive"))
      (node (ref "CST") (pin "2") (pinfunction "2_2") (pintype "passive"))
      (node (ref "CV1") (pin "-") (pinfunction "-_-") (pintype "passive"))
      (node (ref "CW1") (pin "2") (pinfunction "2_2") (pintype "passive"))
      (node (ref "CW2") (pin "2") (pinfunction "2_2") (pintype "passive"))
      (node (ref "D24V22F5") (pin "P$GND1") (pinfunction "GND_P$GND1") (pintype "bidirectional"))
      (node (ref "D24V22F5") (pin "P$GND2") (pinfunction "GND2_P$GND2") (pintype "bidirectional"))
      (node (ref "D24V50F5") (pin "P$GND") (pinfunction "GND_P$GND") (pintype "bidirectional"))
      (node (ref "D24V50F5") (pin "P$GND2") (pinfunction "GND2_P$GND2") (pintype "bidirectional"))
      (node (ref "DP") (pin "A") (pinfunction "A_A") (pintype "passive"))
      (node (ref "ESP8266") (pin "GND") (pinfunction "GND_GND") (pintype "bidirectional"))
      (node (ref "I2C") (pin "1") (pinfunction "1_1") (pintype "bidirectional"))
      (node (ref "IC1") (pin "7") (pinfunction "GND_7") (pintype "power_in"))
      (node (ref "IMU") (pin "1") (pinfunction "1_1") (pintype "bidirectional"))
      (node (ref "J1") (pin "2") (pinfunction "2_2") (pintype "passive"))
      (node (ref "LED_PWR") (pin "C") (pinfunction "C_C") (pintype "passive"))
      (node (ref "LED_STATUS") (pin "C") (pinfunction "C_C") (pintype "passive"))
      (node (ref "LEFT_MOTOR") (pin "3") (pinfunction "3_3") (pintype "passive"))
      (node (ref "LINE_PWR") (pin "1") (pinfunction "1_1") (pintype "bidirectional"))
      (node (ref "POWER") (pin "P$1") (pinfunction "1_P$1") (pintype "passive"))
      (node (ref "POWER2") (pin "P$1") (pinfunction "1_P$1") (pintype "passive"))
      (node (ref "PWR") (pin "1") (pinfunction "1_1") (pintype "passive"))
      (node (ref "PWR") (pin "2") (pinfunction "2_2") (pintype "passive"))
      (node (ref "Q2") (pin "1") (pinfunction "S_1") (pintype "passive"))
      (node (ref "Q2") (pin "3") (pinfunction "S_3") (pintype "passive"))
      (node (ref "QBZ") (pin "2") (pinfunction "S_2") (pintype "passive"))
      (node (ref "RBZ2") (pin "1") (pinfunction "1_1") (pintype "passive"))
      (node (ref "REG_3V3") (pin "1") (pinfunction "GND_1") (pintype "passive"))
      (node (ref "RIGHT_MOTOR") (pin "3") (pinfunction "3_3") (pintype "passive"))
      (node (ref "RIR5") (pin "1") (pinfunction "1_1") (pintype "passive"))
      (node (ref "RQ2A") (pin "1") (pinfunction "1_1") (pintype "passive"))
      (node (ref "RST") (pin "1") (pinfunction "1_1") (pintype "passive"))
      (node (ref "RX2") (pin "1") (pinfunction "1_1") (pintype "passive"))
      (node (ref "SERIAL") (pin "1") (pinfunction "1_1") (pintype "bidirectional"))
      (node (ref "SERVO1") (pin "1") (pinfunction "1_1") (pintype "passive"))
      (node (ref "SERVO2") (pin "1") (pinfunction "1_1") (pintype "passive"))
      (node (ref "SERVO3") (pin "1") (pinfunction "1_1") (pintype "passive"))
      (node (ref "SERVO4") (pin "1") (pinfunction "1_1") (pintype "passive"))
      (node (ref "SERVO5") (pin "1") (pinfunction "1_1") (pintype "passive"))
      (node (ref "SPI") (pin "1") (pinfunction "1_1") (pintype "bidirectional"))
      (node (ref "TEENSY") (pin "GND") (pinfunction "GND_GND") (pintype "power_in"))
      (node (ref "TEENSY") (pin "GND1") (pinfunction "GND_GND1") (pintype "power_in"))
      (node (ref "UC_OP") (pin "4") (pinfunction "VSS_4") (pintype "passive"))
      (node (ref "UM") (pin "10") (pinfunction "PGND2_10") (pintype "bidirectional"))
      (node (ref "UM") (pin "18") (pinfunction "GND_18") (pintype "bidirectional"))
      (node (ref "UM") (pin "3") (pinfunction "PGND1_3") (pintype "bidirectional"))
      (node (ref "UM") (pin "4") (pinfunction "PGND1_4") (pintype "bidirectional"))
      (node (ref "UM") (pin "9") (pinfunction "PGND2_9") (pintype "bidirectional"))
      (node (ref "X-ADC") (pin "1") (pinfunction "1_1") (pintype "passive"))
    )
    (net (code "63") (name "Net-(BUZZER-Pad1)") (class "Default")
      (node (ref "BUZZER") (pin "1") (pinfunction "1_1") (pintype "passive"))
      (node (ref "RBZ1") (pin "2") (pinfunction "2_2") (pintype "passive"))
    )
    (net (code "64") (name "Net-(CM3-Pad1)") (class "Default")
      (node (ref "CM3") (pin "1") (pinfunction "1_1") (pintype "passive"))
      (node (ref "RM") (pin "1") (pinfunction "1_1") (pintype "passive"))
    )
    (net (code "65") (name "Net-(IR-Pad1)") (class "Default")
      (node (ref "IR") (pin "1") (pinfunction "1_1") (pintype "bidirectional"))
      (node (ref "IR") (pin "4") (pinfunction "4_4") (pintype "bidirectional"))
      (node (ref "Q2") (pin "5") (pinfunction "D_5") (pintype "passive"))
      (node (ref "Q2") (pin "6") (pinfunction "D_6") (pintype "passive"))
    )
    (net (code "66") (name "Net-(IR-Pad3)") (class "Default")
      (node (ref "IR") (pin "3") (pinfunction "3_3") (pintype "bidirectional"))
      (node (ref "RIR1") (pin "2") (pinfunction "2_2") (pintype "passive"))
    )
    (net (code "67") (name "Net-(IR-Pad6)") (class "Default")
      (node (ref "IR") (pin "6") (pinfunction "6_6") (pintype "bidirectional"))
      (node (ref "RIR2") (pin "2") (pinfunction "2_2") (pintype "passive"))
    )
    (net (code "68") (name "Net-(LED_PWR-PadA)") (class "Default")
      (node (ref "LED_PWR") (pin "A") (pinfunction "A_A") (pintype "passive"))
      (node (ref "RL2") (pin "1") (pinfunction "1_1") (pintype "passive"))
    )
    (net (code "69") (name "Net-(LED_STATUS-PadA)") (class "Default")
      (node (ref "LED_STATUS") (pin "A") (pinfunction "A_A") (pintype "passive"))
      (node (ref "RL1") (pin "1") (pinfunction "1_1") (pintype "passive"))
    )
    (net (code "70") (name "Net-(Q1-G)") (class "Default")
      (node (ref "CQ2A") (pin "1") (pinfunction "1_1") (pintype "passive"))
      (node (ref "PWR") (pin "3") (pinfunction "3_3") (pintype "passive"))
      (node (ref "PWR") (pin "4") (pinfunction "4_4") (pintype "passive"))
      (node (ref "Q1") (pin "1") (pinfunction "G_1") (pintype "passive"))
      (node (ref "Q2") (pin "7") (pinfunction "D_7") (pintype "passive"))
      (node (ref "Q2") (pin "8") (pinfunction "D_8") (pintype "passive"))
      (node (ref "RQ1") (pin "1") (pinfunction "1_1") (pintype "passive"))
    )
    (net (code "71") (name "Net-(Q1-S)") (class "Default")
      (node (ref "DP") (pin "C") (pinfunction "C_C") (pintype "passive"))
      (node (ref "MAIN_FUSE") (pin "PIN1") (pinfunction "PIN1_PIN1") (pintype "bidirectional"))
      (node (ref "Q1") (pin "3") (pinfunction "S_3") (pintype "passive"))
      (node (ref "RQ1") (pin "2") (pinfunction "2_2") (pintype "passive"))
    )
    (net (code "72") (name "Net-(QBZ-D)") (class "Default")
      (node (ref "QBZ") (pin "3") (pinfunction "D_3") (pintype "passive"))
      (node (ref "RBZ1") (pin "1") (pinfunction "1_1") (pintype "passive"))
    )
    (net (code "73") (name "Net-(RS1-Pad2)") (class "Default")
      (node (ref "RS1") (pin "2") (pinfunction "2_2") (pintype "passive"))
      (node (ref "SERVO1") (pin "3") (pinfunction "3_3") (pintype "passive"))
    )
    (net (code "74") (name "Net-(RS2-Pad2)") (class "Default")
      (node (ref "RS2") (pin "2") (pinfunction "2_2") (pintype "passive"))
      (node (ref "SERVO2") (pin "3") (pinfunction "3_3") (pintype "passive"))
    )
    (net (code "75") (name "Net-(RS3-Pad2)") (class "Default")
      (node (ref "RS3") (pin "2") (pinfunction "2_2") (pintype "passive"))
      (node (ref "SERVO3") (pin "3") (pinfunction "3_3") (pintype "passive"))
    )
    (net (code "76") (name "Net-(RS4-Pad2)") (class "Default")
      (node (ref "RS4") (pin "2") (pinfunction "2_2") (pintype "passive"))
      (node (ref "SERVO4") (pin "3") (pinfunction "3_3") (pintype "passive"))
    )
    (net (code "77") (name "Net-(RS5-Pad2)") (class "Default")
      (node (ref "RS5") (pin "2") (pinfunction "2_2") (pintype "passive"))
      (node (ref "SERVO5") (pin "3") (pinfunction "3_3") (pintype "passive"))
    )
    (net (code "78") (name "Net-(RX1-Pad2)") (class "Default")
      (node (ref "RX1") (pin "2") (pinfunction "2_2") (pintype "passive"))
      (node (ref "X-ADC") (pin "3") (pinfunction "3_3") (pintype "passive"))
    )
    (net (code "79") (name "Net-(SWITCH-O1)") (class "Default")
      (node (ref "MAIN_FUSE") (pin "PIN2") (pinfunction "PIN2_PIN2") (pintype "bidirectional"))
      (node (ref "SWITCH") (pin "P$1") (pinfunction "O1_P$1") (pintype "passive"))
    )
    (net (code "80") (name "Net-(UC1-FILT)") (class "Default")
      (node (ref "CC4") (pin "1") (pinfunction "1_1") (pintype "passive"))
      (node (ref "UC1") (pin "6") (pinfunction "FILT_6") (pintype "bidirectional"))
    )
    (net (code "81") (name "Net-(UC1-VOUT)") (class "Default")
      (node (ref "RC5") (pin "1") (pinfunction "1_1") (pintype "passive"))
      (node (ref "UC1") (pin "7") (pinfunction "VOUT_7") (pintype "bidirectional"))
    )
    (net (code "82") (name "Net-(UC2-FILT)") (class "Default")
      (node (ref "CC6") (pin "1") (pinfunction "1_1") (pintype "passive"))
      (node (ref "UC2") (pin "6") (pinfunction "FILT_6") (pintype "bidirectional"))
    )
    (net (code "83") (name "Net-(UC2-VOUT)") (class "Default")
      (node (ref "RC3") (pin "1") (pinfunction "1_1") (pintype "passive"))
      (node (ref "UC2") (pin "7") (pinfunction "VOUT_7") (pintype "bidirectional"))
    )
    (net (code "84") (name "Net-(UC_OP-VINA_+)") (class "Default")
      (node (ref "CC1") (pin "1") (pinfunction "1_1") (pintype "passive"))
      (node (ref "RC1") (pin "1") (pinfunction "1_1") (pintype "passive"))
      (node (ref "RC2") (pin "2") (pinfunction "2_2") (pintype "passive"))
      (node (ref "UC_OP") (pin "3") (pinfunction "VINA_+_3") (pintype "input"))
      (node (ref "UC_OP") (pin "5") (pinfunction "VINB_+_5") (pintype "input"))
    )
    (net (code "85") (name "unconnected-(D24V22F5-EN-PadP$EN)") (class "Default")
      (node (ref "D24V22F5") (pin "P$EN") (pinfunction "EN_P$EN") (pintype "bidirectional"))
    )
    (net (code "86") (name "unconnected-(D24V22F5-PG-PadP$PG)") (class "Default")
      (node (ref "D24V22F5") (pin "P$PG") (pinfunction "PG_P$PG") (pintype "bidirectional"))
    )
    (net (code "87") (name "unconnected-(D24V50F5-EN-PadP$EN)") (class "Default")
      (node (ref "D24V50F5") (pin "P$EN") (pinfunction "EN_P$EN") (pintype "bidirectional"))
    )
    (net (code "88") (name "unconnected-(ESP8266-PadGPIO0)") (class "Default")
      (node (ref "ESP8266") (pin "GPIO0") (pinfunction "GPIO0_GPIO0") (pintype "bidirectional"))
    )
    (net (code "89") (name "unconnected-(ESP8266-PadGPIO2)") (class "Default")
      (node (ref "ESP8266") (pin "GPIO2") (pinfunction "GPIO2_GPIO2") (pintype "bidirectional"))
    )
    (net (code "90") (name "unconnected-(I2C-Pad6)") (class "Default")
      (node (ref "I2C") (pin "6") (pinfunction "6_6") (pintype "bidirectional"))
    )
    (net (code "91") (name "unconnected-(IMU-Pad5)") (class "Default")
      (node (ref "IMU") (pin "5") (pinfunction "5_5") (pintype "bidirectional"))
    )
    (net (code "92") (name "unconnected-(IMU-Pad6)") (class "Default")
      (node (ref "IMU") (pin "6") (pinfunction "6_6") (pintype "bidirectional"))
    )
    (net (code "93") (name "unconnected-(LINE_PWR-Pad5)") (class "Default")
      (node (ref "LINE_PWR") (pin "5") (pinfunction "5_5") (pintype "bidirectional"))
    )
    (net (code "94") (name "unconnected-(LINE_PWR-Pad6)") (class "Default")
      (node (ref "LINE_PWR") (pin "6") (pinfunction "6_6") (pintype "bidirectional"))
    )
    (net (code "95") (name "unconnected-(SERIAL-Pad6)") (class "Default")
      (node (ref "SERIAL") (pin "6") (pinfunction "6_6") (pintype "bidirectional"))
    )
    (net (code "96") (name "unconnected-(SPI-Pad5)") (class "Default")
      (node (ref "SPI") (pin "5") (pinfunction "5_5") (pintype "bidirectional"))
    )
    (net (code "97") (name "unconnected-(SWITCH-S3-PadP$3)") (class "Default")
      (node (ref "SWITCH") (pin "P$3") (pinfunction "S3_P$3") (pintype "passive"))
    )
  )
)
